# BoosterBoard.net
KiCad netlist of a schematic drawn in EAGLE
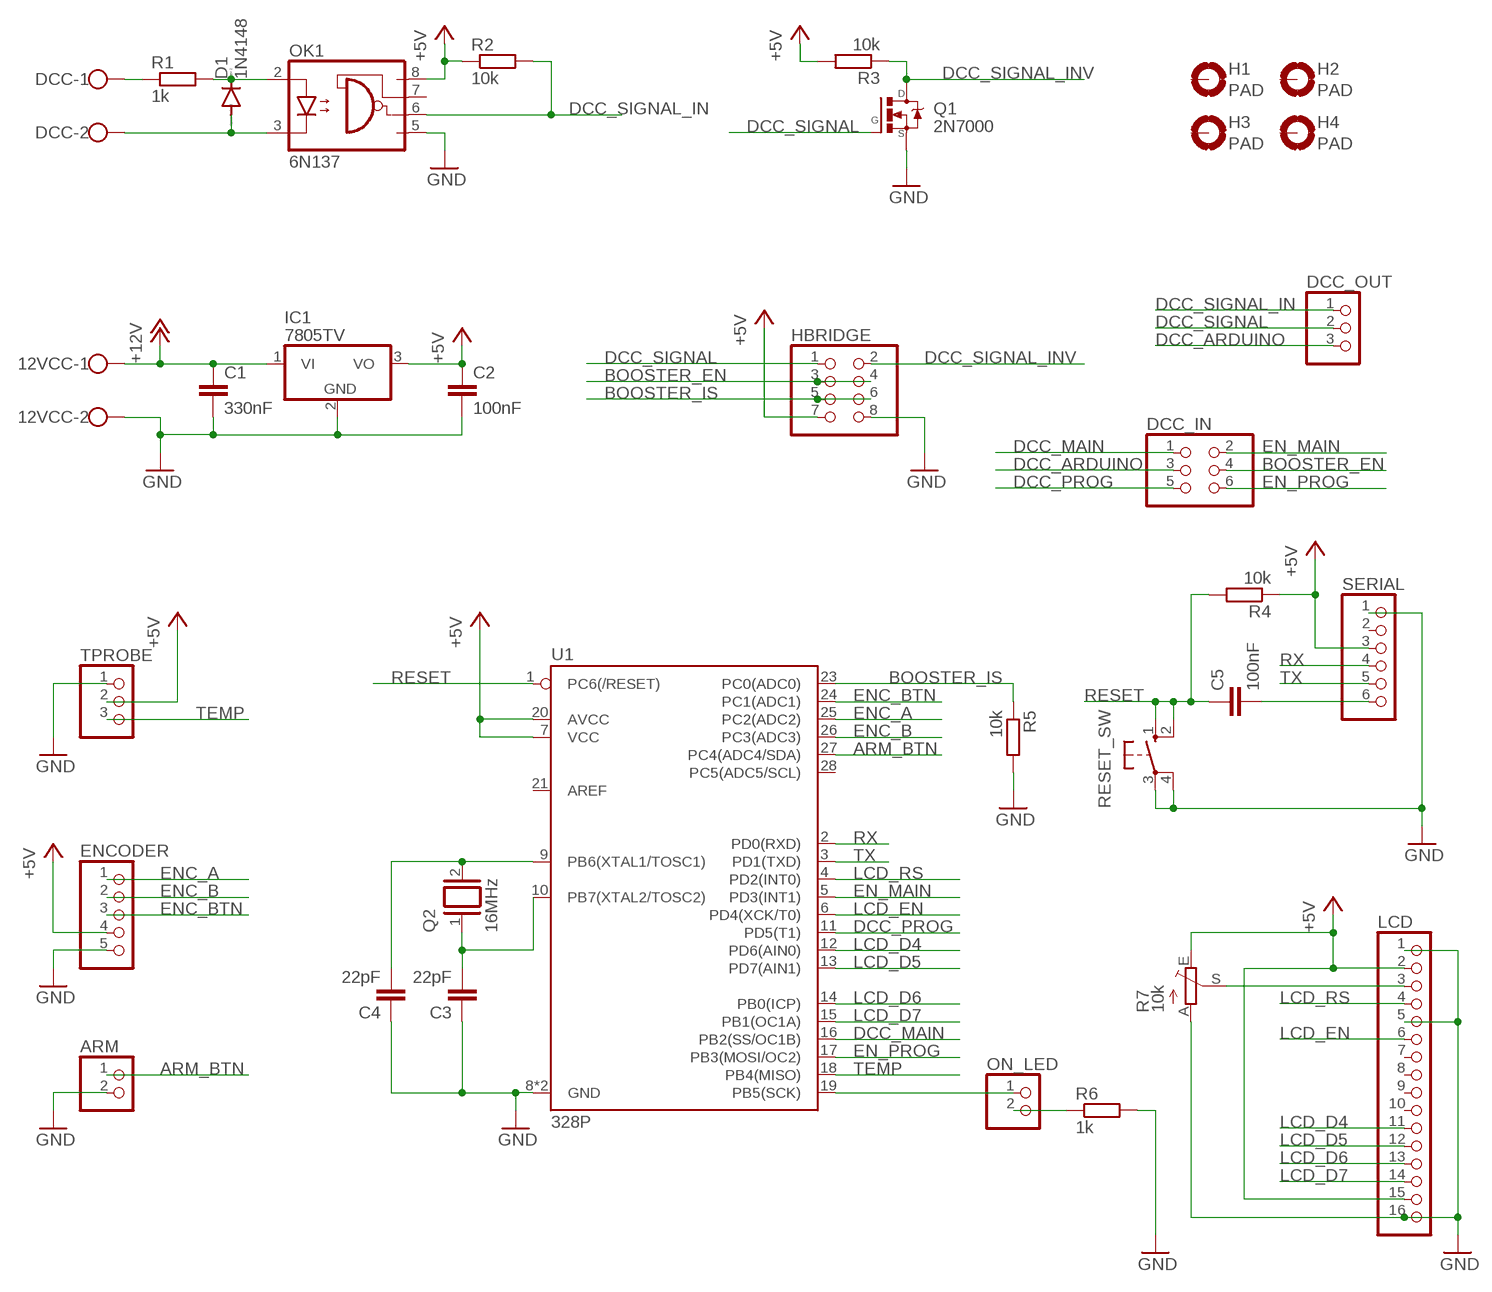
[diagram p0: schematic, sheet 1]

(export (version "E")
  (design (tool "Eeschema 10.0.6"))
  (components
    (comp (ref "12VCC")
      (value "W237-102")
      (footprint "eagle-import:W237-102")
      (fields (field (name "MPN") "237-102"))
      (libsource (lib "eagle-import") (part "W237-102"))
    )
    (comp (ref "ARM")
      (value "PINHD-1X2")
      (footprint "eagle-import:1X02")
      (libsource (lib "eagle-import") (part "PINHD-1X2"))
    )
    (comp (ref "C1")
      (value "330nF")
      (footprint "eagle-import:C050-030X075")
      (libsource (lib "eagle-import") (part "C-EU050-030X075"))
    )
    (comp (ref "C2")
      (value "100nF")
      (footprint "eagle-import:C050-030X075")
      (libsource (lib "eagle-import") (part "C-EU050-030X075"))
    )
    (comp (ref "C3")
      (value "22pF")
      (footprint "eagle-import:C025-025X050")
      (libsource (lib "eagle-import") (part "C-EU025-025X050"))
    )
    (comp (ref "C4")
      (value "22pF")
      (footprint "eagle-import:C025-025X050")
      (libsource (lib "eagle-import") (part "C-EU025-025X050"))
    )
    (comp (ref "C5")
      (value "100nF")
      (footprint "eagle-import:C050-030X075")
      (libsource (lib "eagle-import") (part "C-EU050-030X075"))
    )
    (comp (ref "D1")
      (value "1N4148")
      (footprint "eagle-import:DO35-10")
      (libsource (lib "eagle-import") (part "1N4148DO35-10"))
    )
    (comp (ref "DCC")
      (value "W237-102")
      (footprint "eagle-import:W237-102")
      (fields (field (name "MPN") "237-102"))
      (libsource (lib "eagle-import") (part "W237-102"))
    )
    (comp (ref "DCC_IN")
      (value "PINHD-2X3")
      (footprint "eagle-import:2X03")
      (libsource (lib "eagle-import") (part "PINHD-2X3"))
    )
    (comp (ref "DCC_OUT")
      (value "PINHD-1X3")
      (footprint "eagle-import:1X03")
      (libsource (lib "eagle-import") (part "PINHD-1X3"))
    )
    (comp (ref "ENCODER")
      (value "PINHD-1X5")
      (footprint "eagle-import:1X05")
      (libsource (lib "eagle-import") (part "PINHD-1X5"))
    )
    (comp (ref "H1")
      (value "PAD")
      (footprint "eagle-import:3,0-PAD")
      (libsource (lib "eagle-import") (part "MOUNT-PAD-ROUND3.0"))
    )
    (comp (ref "H2")
      (value "PAD")
      (footprint "eagle-import:3,0-PAD")
      (libsource (lib "eagle-import") (part "MOUNT-PAD-ROUND3.0"))
    )
    (comp (ref "H3")
      (value "PAD")
      (footprint "eagle-import:3,0-PAD")
      (libsource (lib "eagle-import") (part "MOUNT-PAD-ROUND3.0"))
    )
    (comp (ref "H4")
      (value "PAD")
      (footprint "eagle-import:3,0-PAD")
      (libsource (lib "eagle-import") (part "MOUNT-PAD-ROUND3.0"))
    )
    (comp (ref "HBRIDGE")
      (value "PINHD-2X4")
      (footprint "eagle-import:2X04")
      (libsource (lib "eagle-import") (part "PINHD-2X4"))
    )
    (comp (ref "IC1")
      (value "7805TV")
      (footprint "eagle-import:TO220V")
      (libsource (lib "eagle-import") (part "78TV05"))
    )
    (comp (ref "LCD")
      (value "PINHD-1X16")
      (footprint "eagle-import:1X16")
      (libsource (lib "eagle-import") (part "PINHD-1X16"))
    )
    (comp (ref "OK1")
      (value "6N137")
      (footprint "eagle-import:DIL08")
      (libsource (lib "eagle-import") (part "6N137"))
    )
    (comp (ref "ON_LED")
      (value "PINHD-1X2")
      (footprint "eagle-import:1X02")
      (libsource (lib "eagle-import") (part "PINHD-1X2"))
    )
    (comp (ref "Q1")
      (value "2N7000")
      (footprint "eagle-import:TO-92")
      (libsource (lib "eagle-import") (part "2N7000"))
    )
    (comp (ref "Q2")
      (value "16MHz")
      (footprint "eagle-import:QS")
      (libsource (lib "eagle-import") (part "XTAL/S"))
    )
    (comp (ref "R1")
      (value "1k")
      (footprint "eagle-import:0207_2V")
      (libsource (lib "eagle-import") (part "R-EU_0207/2V"))
    )
    (comp (ref "R2")
      (value "10k")
      (footprint "eagle-import:0207_2V")
      (libsource (lib "eagle-import") (part "R-EU_0207/2V"))
    )
    (comp (ref "R3")
      (value "10k")
      (footprint "eagle-import:0207_2V")
      (libsource (lib "eagle-import") (part "R-EU_0207/2V"))
    )
    (comp (ref "R4")
      (value "10k")
      (footprint "eagle-import:0207_2V")
      (libsource (lib "eagle-import") (part "R-EU_0207/2V"))
    )
    (comp (ref "R5")
      (value "10k")
      (footprint "eagle-import:0207_2V")
      (libsource (lib "eagle-import") (part "R-EU_0207/2V"))
    )
    (comp (ref "R6")
      (value "1k")
      (footprint "eagle-import:0207_2V")
      (libsource (lib "eagle-import") (part "R-EU_0207/2V"))
    )
    (comp (ref "R7")
      (value "10k")
      (footprint "eagle-import:B64W")
      (libsource (lib "eagle-import") (part "TRIM_EU-B64W"))
    )
    (comp (ref "RESET_SW")
      (value "10-XX")
      (footprint "eagle-import:B3F-10XX")
      (fields (field (name "MPN") "B3F-1000"))
      (libsource (lib "eagle-import") (part "10-XX"))
    )
    (comp (ref "SERIAL")
      (value "PINHD-1X6")
      (footprint "eagle-import:1X06")
      (libsource (lib "eagle-import") (part "PINHD-1X6"))
    )
    (comp (ref "TPROBE")
      (value "PINHD-1X3")
      (footprint "eagle-import:1X03")
      (libsource (lib "eagle-import") (part "PINHD-1X3"))
    )
    (comp (ref "U1")
      (value "328P")
      (footprint "eagle-import:DIP28")
      (libsource (lib "eagle-import") (part "ATMEGA328P_PDIP"))
    )
  )
  (nets
    (net (code "1") (name "+5V") (class "Default")
      (node (ref "C2") (pin "1") (pinfunction "1_1") (pintype "passive"))
      (node (ref "ENCODER") (pin "4") (pinfunction "4_4") (pintype "passive"))
      (node (ref "HBRIDGE") (pin "7") (pinfunction "7_7") (pintype "passive"))
      (node (ref "IC1") (pin "3") (pinfunction "VO_3") (pintype "passive"))
      (node (ref "LCD") (pin "15") (pinfunction "15_15") (pintype "passive"))
      (node (ref "LCD") (pin "2") (pinfunction "2_2") (pintype "passive"))
      (node (ref "OK1") (pin "8") (pinfunction "VCC_8") (pintype "passive"))
      (node (ref "R2") (pin "1") (pinfunction "1_1") (pintype "passive"))
      (node (ref "R3") (pin "2") (pinfunction "2_2") (pintype "passive"))
      (node (ref "R4") (pin "1") (pinfunction "1_1") (pintype "passive"))
      (node (ref "R7") (pin "E") (pinfunction "E_E") (pintype "passive"))
      (node (ref "SERIAL") (pin "3") (pinfunction "3_3") (pintype "passive"))
      (node (ref "TPROBE") (pin "2") (pinfunction "2_2") (pintype "passive"))
      (node (ref "U1") (pin "20") (pinfunction "AVCC_20") (pintype "bidirectional"))
      (node (ref "U1") (pin "7") (pinfunction "VCC_7") (pintype "bidirectional"))
    )
    (net (code "2") (name "+12V") (class "Default")
      (node (ref "12VCC") (pin "1") (pinfunction "KL_1") (pintype "passive"))
      (node (ref "C1") (pin "1") (pinfunction "1_1") (pintype "passive"))
      (node (ref "IC1") (pin "1") (pinfunction "VI_1") (pintype "input"))
    )
    (net (code "3") (name "/ARM_BTN") (class "Default")
      (node (ref "ARM") (pin "1") (pinfunction "1_1") (pintype "passive"))
      (node (ref "U1") (pin "27") (pinfunction "PC4(ADC4/SDA)_27") (pintype "bidirectional"))
    )
    (net (code "4") (name "/BOOSTER_EN") (class "Default")
      (node (ref "DCC_IN") (pin "4") (pinfunction "4_4") (pintype "passive"))
      (node (ref "HBRIDGE") (pin "3") (pinfunction "3_3") (pintype "passive"))
      (node (ref "HBRIDGE") (pin "4") (pinfunction "4_4") (pintype "passive"))
    )
    (net (code "5") (name "/BOOSTER_IS") (class "Default")
      (node (ref "HBRIDGE") (pin "5") (pinfunction "5_5") (pintype "passive"))
      (node (ref "HBRIDGE") (pin "6") (pinfunction "6_6") (pintype "passive"))
      (node (ref "R5") (pin "1") (pinfunction "1_1") (pintype "passive"))
      (node (ref "U1") (pin "23") (pinfunction "PC0(ADC0)_23") (pintype "bidirectional"))
    )
    (net (code "6") (name "/DCC_ARDUINO") (class "Default")
      (node (ref "DCC_IN") (pin "3") (pinfunction "3_3") (pintype "passive"))
      (node (ref "DCC_OUT") (pin "3") (pinfunction "3_3") (pintype "passive"))
    )
    (net (code "7") (name "/DCC_MAIN") (class "Default")
      (node (ref "DCC_IN") (pin "1") (pinfunction "1_1") (pintype "passive"))
      (node (ref "U1") (pin "16") (pinfunction "PB2(SS/OC1B)_16") (pintype "bidirectional"))
    )
    (net (code "8") (name "/DCC_PROG") (class "Default")
      (node (ref "DCC_IN") (pin "5") (pinfunction "5_5") (pintype "passive"))
      (node (ref "U1") (pin "11") (pinfunction "PD5(T1)_11") (pintype "bidirectional"))
    )
    (net (code "9") (name "/DCC_SIGNAL") (class "Default")
      (node (ref "DCC_OUT") (pin "2") (pinfunction "2_2") (pintype "passive"))
      (node (ref "HBRIDGE") (pin "1") (pinfunction "1_1") (pintype "passive"))
      (node (ref "Q1") (pin "2") (pinfunction "G_2") (pintype "passive"))
    )
    (net (code "10") (name "/DCC_SIGNAL_IN") (class "Default")
      (node (ref "DCC_OUT") (pin "1") (pinfunction "1_1") (pintype "passive"))
      (node (ref "OK1") (pin "6") (pinfunction "VO_6") (pintype "passive"))
      (node (ref "R2") (pin "2") (pinfunction "2_2") (pintype "passive"))
    )
    (net (code "11") (name "/DCC_SIGNAL_INV") (class "Default")
      (node (ref "HBRIDGE") (pin "2") (pinfunction "2_2") (pintype "passive"))
      (node (ref "Q1") (pin "3") (pinfunction "D_3") (pintype "passive"))
      (node (ref "R3") (pin "1") (pinfunction "1_1") (pintype "passive"))
    )
    (net (code "12") (name "/ENC_A") (class "Default")
      (node (ref "ENCODER") (pin "1") (pinfunction "1_1") (pintype "passive"))
      (node (ref "U1") (pin "25") (pinfunction "PC2(ADC2)_25") (pintype "bidirectional"))
    )
    (net (code "13") (name "/ENC_B") (class "Default")
      (node (ref "ENCODER") (pin "2") (pinfunction "2_2") (pintype "passive"))
      (node (ref "U1") (pin "26") (pinfunction "PC3(ADC3)_26") (pintype "bidirectional"))
    )
    (net (code "14") (name "/ENC_BTN") (class "Default")
      (node (ref "ENCODER") (pin "3") (pinfunction "3_3") (pintype "passive"))
      (node (ref "U1") (pin "24") (pinfunction "PC1(ADC1)_24") (pintype "bidirectional"))
    )
    (net (code "15") (name "/EN_MAIN") (class "Default")
      (node (ref "DCC_IN") (pin "2") (pinfunction "2_2") (pintype "passive"))
      (node (ref "U1") (pin "5") (pinfunction "PD3(INT1)_5") (pintype "bidirectional"))
    )
    (net (code "16") (name "/EN_PROG") (class "Default")
      (node (ref "DCC_IN") (pin "6") (pinfunction "6_6") (pintype "passive"))
      (node (ref "U1") (pin "17") (pinfunction "PB3(MOSI/OC2)_17") (pintype "bidirectional"))
    )
    (net (code "17") (name "/LCD_D4") (class "Default")
      (node (ref "LCD") (pin "11") (pinfunction "11_11") (pintype "passive"))
      (node (ref "U1") (pin "12") (pinfunction "PD6(AIN0)_12") (pintype "bidirectional"))
    )
    (net (code "18") (name "/LCD_D5") (class "Default")
      (node (ref "LCD") (pin "12") (pinfunction "12_12") (pintype "passive"))
      (node (ref "U1") (pin "13") (pinfunction "PD7(AIN1)_13") (pintype "bidirectional"))
    )
    (net (code "19") (name "/LCD_D6") (class "Default")
      (node (ref "LCD") (pin "13") (pinfunction "13_13") (pintype "passive"))
      (node (ref "U1") (pin "14") (pinfunction "PB0(ICP)_14") (pintype "bidirectional"))
    )
    (net (code "20") (name "/LCD_D7") (class "Default")
      (node (ref "LCD") (pin "14") (pinfunction "14_14") (pintype "passive"))
      (node (ref "U1") (pin "15") (pinfunction "PB1(OC1A)_15") (pintype "bidirectional"))
    )
    (net (code "21") (name "/LCD_EN") (class "Default")
      (node (ref "LCD") (pin "6") (pinfunction "6_6") (pintype "passive"))
      (node (ref "U1") (pin "6") (pinfunction "PD4(XCK/T0)_6") (pintype "bidirectional"))
    )
    (net (code "22") (name "/LCD_RS") (class "Default")
      (node (ref "LCD") (pin "4") (pinfunction "4_4") (pintype "passive"))
      (node (ref "U1") (pin "4") (pinfunction "PD2(INT0)_4") (pintype "bidirectional"))
    )
    (net (code "23") (name "/RESET") (class "Default")
      (node (ref "C5") (pin "1") (pinfunction "1_1") (pintype "passive"))
      (node (ref "R4") (pin "2") (pinfunction "2_2") (pintype "passive"))
      (node (ref "RESET_SW") (pin "1") (pinfunction "S_1") (pintype "passive"))
      (node (ref "RESET_SW") (pin "2") (pinfunction "S1_2") (pintype "passive"))
      (node (ref "U1") (pin "1") (pinfunction "PC6(/RESET)_1") (pintype "bidirectional"))
    )
    (net (code "24") (name "/RX") (class "Default")
      (node (ref "SERIAL") (pin "4") (pinfunction "4_4") (pintype "passive"))
      (node (ref "U1") (pin "2") (pinfunction "PD0(RXD)_2") (pintype "bidirectional"))
    )
    (net (code "25") (name "/TEMP") (class "Default")
      (node (ref "TPROBE") (pin "3") (pinfunction "3_3") (pintype "passive"))
      (node (ref "U1") (pin "18") (pinfunction "PB4(MISO)_18") (pintype "bidirectional"))
    )
    (net (code "26") (name "/TX") (class "Default")
      (node (ref "SERIAL") (pin "5") (pinfunction "5_5") (pintype "passive"))
      (node (ref "U1") (pin "3") (pinfunction "PD1(TXD)_3") (pintype "bidirectional"))
    )
    (net (code "27") (name "GND") (class "Default")
      (node (ref "12VCC") (pin "2") (pinfunction "KL_2") (pintype "passive"))
      (node (ref "ARM") (pin "2") (pinfunction "2_2") (pintype "passive"))
      (node (ref "C1") (pin "2") (pinfunction "2_2") (pintype "passive"))
      (node (ref "C2") (pin "2") (pinfunction "2_2") (pintype "passive"))
      (node (ref "C3") (pin "1") (pinfunction "1_1") (pintype "passive"))
      (node (ref "C4") (pin "1") (pinfunction "1_1") (pintype "passive"))
      (node (ref "ENCODER") (pin "5") (pinfunction "5_5") (pintype "passive"))
      (node (ref "HBRIDGE") (pin "8") (pinfunction "8_8") (pintype "passive"))
      (node (ref "IC1") (pin "2") (pinfunction "GND_2") (pintype "passive"))
      (node (ref "LCD") (pin "1") (pinfunction "1_1") (pintype "passive"))
      (node (ref "LCD") (pin "16") (pinfunction "16_16") (pintype "passive"))
      (node (ref "LCD") (pin "5") (pinfunction "5_5") (pintype "passive"))
      (node (ref "OK1") (pin "5") (pinfunction "GND_5") (pintype "passive"))
      (node (ref "Q1") (pin "1") (pinfunction "S_1") (pintype "passive"))
      (node (ref "R5") (pin "2") (pinfunction "2_2") (pintype "passive"))
      (node (ref "R6") (pin "2") (pinfunction "2_2") (pintype "passive"))
      (node (ref "R7") (pin "A") (pinfunction "A_A") (pintype "passive"))
      (node (ref "RESET_SW") (pin "3") (pinfunction "P_3") (pintype "passive"))
      (node (ref "RESET_SW") (pin "4") (pinfunction "P1_4") (pintype "passive"))
      (node (ref "SERIAL") (pin "1") (pinfunction "1_1") (pintype "passive"))
      (node (ref "TPROBE") (pin "1") (pinfunction "1_1") (pintype "passive"))
      (node (ref "U1") (pin "22") (pinfunction "GND_22") (pintype "bidirectional"))
      (node (ref "U1") (pin "8") (pinfunction "GND_8") (pintype "bidirectional"))
    )
    (net (code "28") (name "Net-(C5-Pad2)") (class "Default")
      (node (ref "C5") (pin "2") (pinfunction "2_2") (pintype "passive"))
      (node (ref "SERIAL") (pin "6") (pinfunction "6_6") (pintype "passive"))
    )
    (net (code "29") (name "Net-(DCCA-KL)") (class "Default")
      (node (ref "DCC") (pin "1") (pinfunction "KL_1") (pintype "passive"))
      (node (ref "R1") (pin "1") (pinfunction "1_1") (pintype "passive"))
    )
    (net (code "30") (name "Net-(DCCB-KL)") (class "Default")
      (node (ref "D1") (pin "A") (pinfunction "A_A") (pintype "passive"))
      (node (ref "DCC") (pin "2") (pinfunction "KL_2") (pintype "passive"))
      (node (ref "OK1") (pin "3") (pinfunction "C_3") (pintype "passive"))
    )
    (net (code "31") (name "Net-(LCD-Pad3)") (class "Default")
      (node (ref "LCD") (pin "3") (pinfunction "3_3") (pintype "passive"))
      (node (ref "R7") (pin "S") (pinfunction "S_S") (pintype "passive"))
    )
    (net (code "32") (name "Net-(OK1-A)") (class "Default")
      (node (ref "D1") (pin "C") (pinfunction "C_C") (pintype "passive"))
      (node (ref "OK1") (pin "2") (pinfunction "A_2") (pintype "passive"))
      (node (ref "R1") (pin "2") (pinfunction "2_2") (pintype "passive"))
    )
    (net (code "33") (name "Net-(ON_LED-Pad2)") (class "Default")
      (node (ref "ON_LED") (pin "2") (pinfunction "2_2") (pintype "passive"))
      (node (ref "R6") (pin "1") (pinfunction "1_1") (pintype "passive"))
    )
    (net (code "34") (name "Net-(U1-PB5(SCK))") (class "Default")
      (node (ref "ON_LED") (pin "1") (pinfunction "1_1") (pintype "passive"))
      (node (ref "U1") (pin "19") (pinfunction "PB5(SCK)_19") (pintype "bidirectional"))
    )
    (net (code "35") (name "Net-(U1-PB6(XTAL1{slash}TOSC1))") (class "Default")
      (node (ref "C4") (pin "2") (pinfunction "2_2") (pintype "passive"))
      (node (ref "Q2") (pin "2") (pinfunction "2_2") (pintype "passive"))
      (node (ref "U1") (pin "9") (pinfunction "PB6(XTAL1/TOSC1)_9") (pintype "bidirectional"))
    )
    (net (code "36") (name "Net-(U1-PB7(XTAL2{slash}TOSC2))") (class "Default")
      (node (ref "C3") (pin "2") (pinfunction "2_2") (pintype "passive"))
      (node (ref "Q2") (pin "1") (pinfunction "1_1") (pintype "passive"))
      (node (ref "U1") (pin "10") (pinfunction "PB7(XTAL2/TOSC2)_10") (pintype "bidirectional"))
    )
    (net (code "37") (name "unconnected-(H1-MOUNT-PadB3,0)") (class "Default")
      (node (ref "H1") (pin "B3,0") (pinfunction "MOUNT_B3,0") (pintype "passive"))
    )
    (net (code "38") (name "unconnected-(H2-MOUNT-PadB3,0)") (class "Default")
      (node (ref "H2") (pin "B3,0") (pinfunction "MOUNT_B3,0") (pintype "passive"))
    )
    (net (code "39") (name "unconnected-(H3-MOUNT-PadB3,0)") (class "Default")
      (node (ref "H3") (pin "B3,0") (pinfunction "MOUNT_B3,0") (pintype "passive"))
    )
    (net (code "40") (name "unconnected-(H4-MOUNT-PadB3,0)") (class "Default")
      (node (ref "H4") (pin "B3,0") (pinfunction "MOUNT_B3,0") (pintype "passive"))
    )
    (net (code "41") (name "unconnected-(LCD-Pad7)") (class "Default")
      (node (ref "LCD") (pin "7") (pinfunction "7_7") (pintype "passive"))
    )
    (net (code "42") (name "unconnected-(LCD-Pad8)") (class "Default")
      (node (ref "LCD") (pin "8") (pinfunction "8_8") (pintype "passive"))
    )
    (net (code "43") (name "unconnected-(LCD-Pad9)") (class "Default")
      (node (ref "LCD") (pin "9") (pinfunction "9_9") (pintype "passive"))
    )
    (net (code "44") (name "unconnected-(LCD-Pad10)") (class "Default")
      (node (ref "LCD") (pin "10") (pinfunction "10_10") (pintype "passive"))
    )
    (net (code "45") (name "unconnected-(OK1-VE-Pad7)") (class "Default")
      (node (ref "OK1") (pin "7") (pinfunction "VE_7") (pintype "passive"))
    )
    (net (code "46") (name "unconnected-(SERIAL-Pad2)") (class "Default")
      (node (ref "SERIAL") (pin "2") (pinfunction "2_2") (pintype "passive"))
    )
    (net (code "47") (name "unconnected-(U1-AREF-Pad21)") (class "Default")
      (node (ref "U1") (pin "21") (pinfunction "AREF_21") (pintype "bidirectional"))
    )
    (net (code "48") (name "unconnected-(U1-PC5(ADC5{slash}SCL)-Pad28)") (class "Default")
      (node (ref "U1") (pin "28") (pinfunction "PC5(ADC5/SCL)_28") (pintype "bidirectional"))
    )
  )
)
